# MAX_M10M_PINOUT.net
KiCad netlist of a schematic drawn in Altium Designer
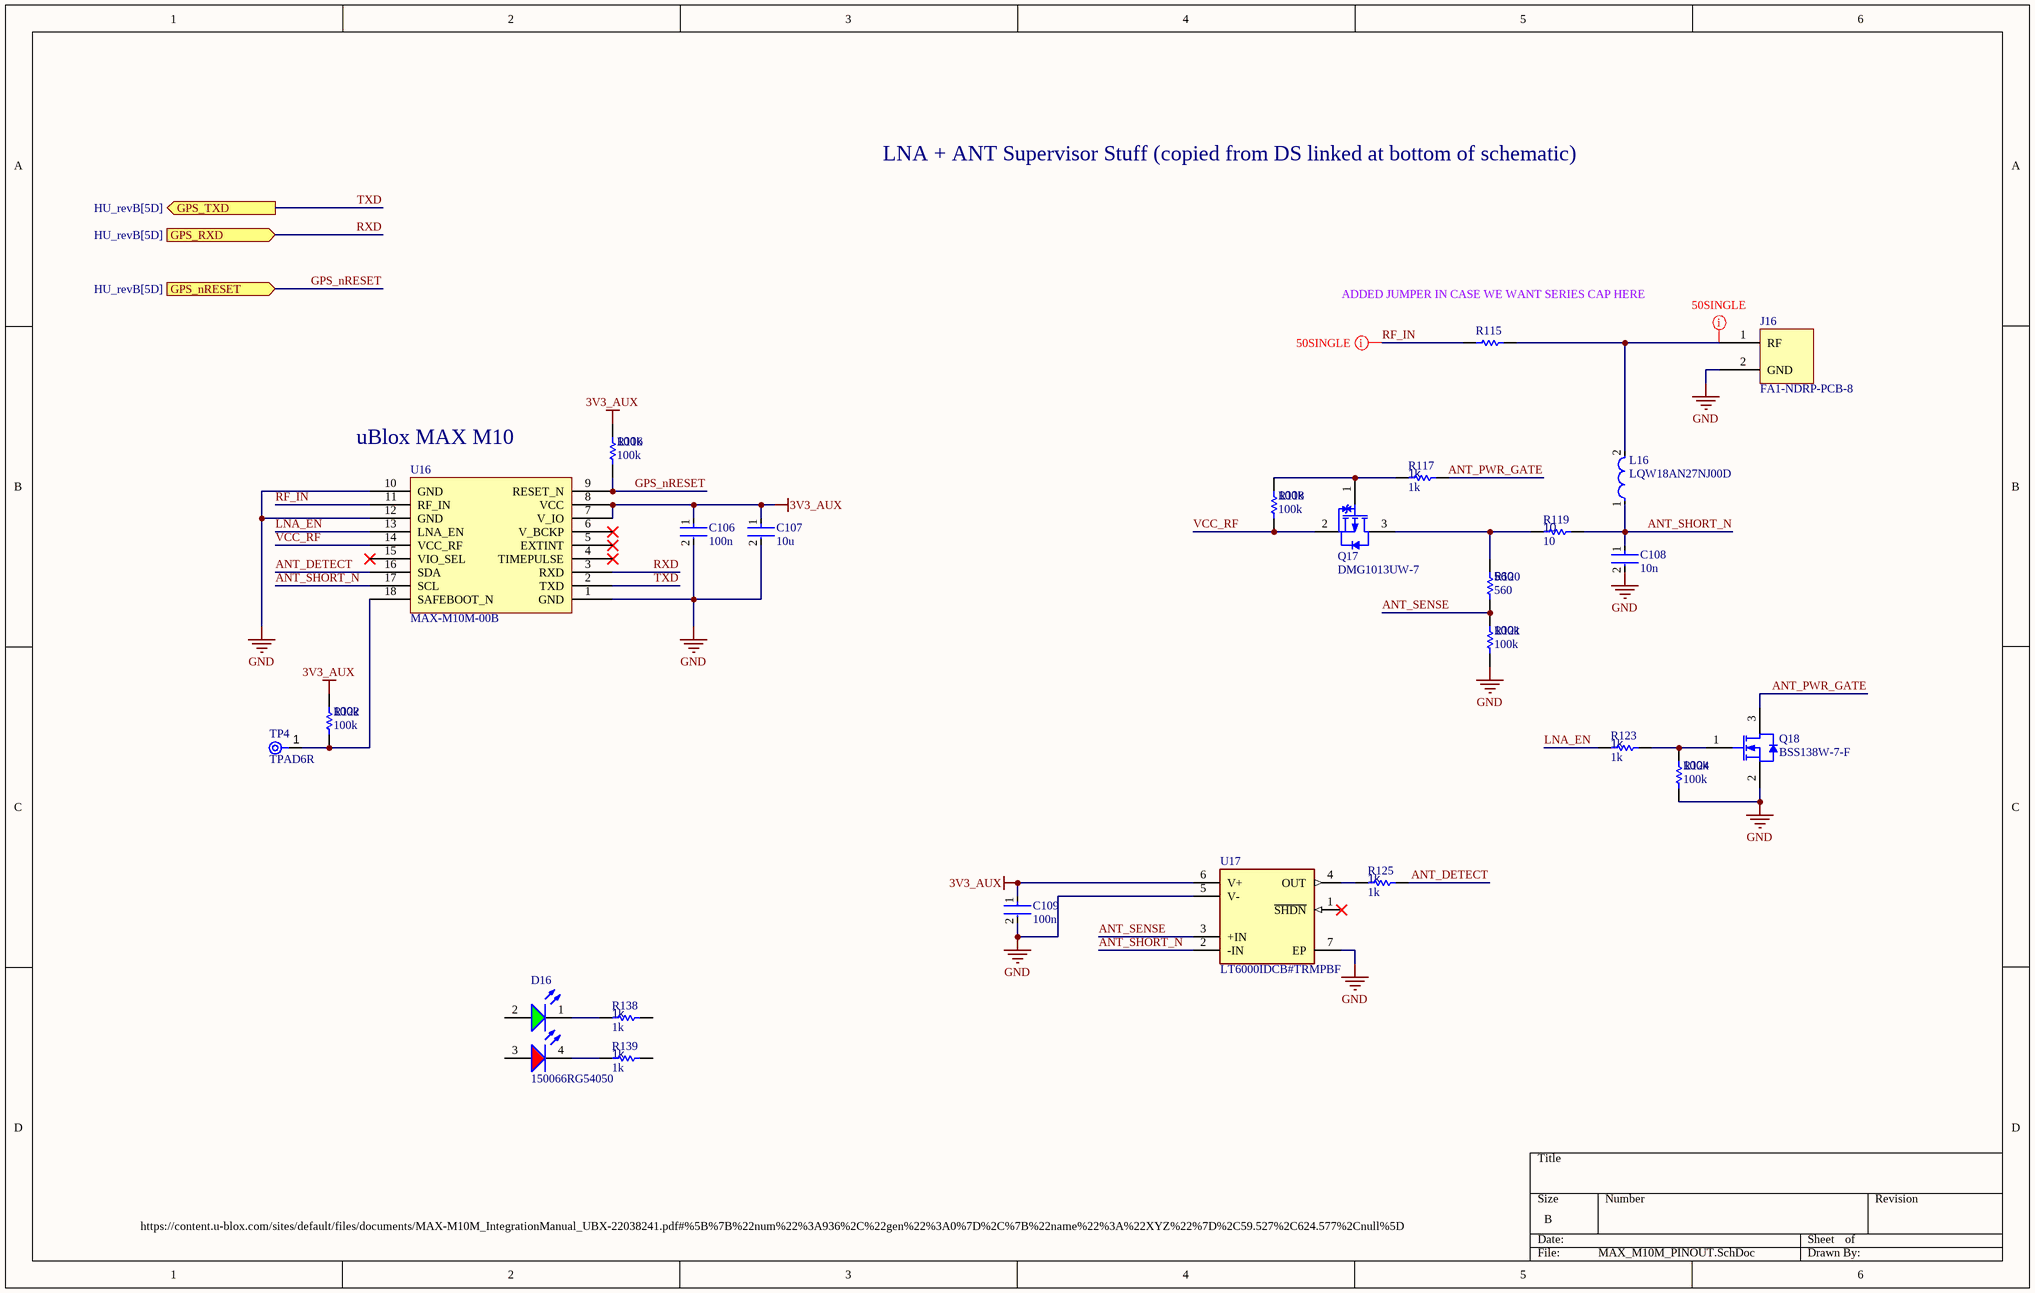
[diagram p0: MAX_M10M_PINOUT.SchDoc]

(export (version "E")
  (design (tool "Eeschema 10.0.6"))
  (components
    (comp (ref "C106")
      (value "100n")
      (footprint "FP-0402-L_1_0_0_05-W_0_5-IPC_A")
      (description "LARGE PADS, 0402 CAP, CHANGE COMMENT TO MATCH REAL P/N")
      (libsource (lib "Space Concordia") (part "b4654b650e69147ec39a6b967a45e02"))
    )
    (comp (ref "C107")
      (value "10u")
      (footprint "FP-0402-L_1_0_0_05-W_0_5-IPC_A")
      (description "LARGE PADS, 0402 CAP, CHANGE COMMENT TO MATCH REAL P/N")
      (libsource (lib "Space Concordia") (part "b4654b650e69147ec39a6b967a45e02"))
    )
    (comp (ref "C108")
      (value "10n")
      (footprint "FP-0402-L_1_0_0_05-W_0_5-IPC_A")
      (description "LARGE PADS, 0402 CAP, CHANGE COMMENT TO MATCH REAL P/N")
      (libsource (lib "Space Concordia") (part "b4654b650e69147ec39a6b967a45e02"))
    )
    (comp (ref "C109")
      (value "100n")
      (footprint "FP-0402-L_1_0_0_05-W_0_5-IPC_A")
      (description "LARGE PADS, 0402 CAP, CHANGE COMMENT TO MATCH REAL P/N")
      (libsource (lib "Space Concordia") (part "b4654b650e69147ec39a6b967a45e02"))
    )
    (comp (ref "D16")
      (value "150066RG54050")
      (footprint "WL-SBCD_0606")
      (description "Led, Red/Grn, 180Mcd/230Mcd, 624Nm/525Nm Rohs Compliant: Yes")
      (fields (field (name "SOURCE") "rgled.SchLib"))
      (libsource (lib "Space Concordia") (part "CMP-004-00034-2"))
    )
    (comp (ref "J16")
      (value "FA1-NDRP-PCB-8")
      (footprint "FA1-NDRP-PCB-8-Footprint-1")
      (description "RF F Connector, Male, Board Mount, Solder Terminal, Plug")
      (libsource (lib "Space Concordia") (part "FA1-NDRP-PCB-8"))
    )
    (comp (ref "L16")
      (value "LQW18AN27NJ00D")
      (footprint "FP-LQW18AN_00-MFG")
      (description "Wire Wound RF Inductor 27nH ±5% 440mA 0.21Ω 0603 (1608)")
      (fields (field (name "TOLERANCE") "5%"))
      (libsource (lib "Altium Content Vault") (part "725321dda6339637d4d059423bc1c3c"))
    )
    (comp (ref "Q17")
      (value "DMG1013UW-7")
      (footprint "DIOD-SOT323-3_V")
      (fields (field (name "MANUFACTURER") "Diodes Inc"))
      (libsource (lib "Altium Content Vault") (part "PEMOS-GSD-3_C"))
    )
    (comp (ref "Q18")
      (value "BSS138W-7-F")
      (footprint "DIOD-SOT323-3_V")
      (fields (field (name "MANUFACTURER") "DiodesIncorporated"))
      (libsource (lib "Altium Content Vault") (part "NEMOS-GSD-3"))
    )
    (comp (ref "R115")
      (value "0402 JUMPER")
      (footprint "RESC1005X40X25ML05T05")
      (description "READ THE NAME")
      (libsource (lib "Space Concordia") (part "CMP-009-00206-2"))
    )
    (comp (ref "R116")
      (value "100k")
      (footprint "R0603B")
      (description "Resistor")
      (fields (field (name "ALTIUM_VALUE") "100k"))
      (libsource (lib "Space Concordia") (part "Resistor"))
    )
    (comp (ref "R117")
      (value "1k")
      (footprint "R0603B")
      (description "Resistor")
      (fields (field (name "ALTIUM_VALUE") "1k"))
      (libsource (lib "Space Concordia") (part "Resistor"))
    )
    (comp (ref "R118")
      (value "100k")
      (footprint "R0603B")
      (description "Resistor")
      (fields (field (name "ALTIUM_VALUE") "100k"))
      (libsource (lib "Space Concordia") (part "Resistor"))
    )
    (comp (ref "R119")
      (value "10")
      (footprint "R0603B")
      (description "Resistor")
      (fields (field (name "ALTIUM_VALUE") "10"))
      (libsource (lib "Space Concordia") (part "Resistor"))
    )
    (comp (ref "R120")
      (value "560")
      (footprint "R0603B")
      (description "Resistor")
      (fields (field (name "ALTIUM_VALUE") "560"))
      (libsource (lib "Space Concordia") (part "Resistor"))
    )
    (comp (ref "R121")
      (value "100k")
      (footprint "R0603B")
      (description "Resistor")
      (fields (field (name "ALTIUM_VALUE") "100k"))
      (libsource (lib "Space Concordia") (part "Resistor"))
    )
    (comp (ref "R122")
      (value "100k")
      (footprint "R0603B")
      (description "Resistor")
      (fields (field (name "ALTIUM_VALUE") "100k"))
      (libsource (lib "Space Concordia") (part "Resistor"))
    )
    (comp (ref "R123")
      (value "1k")
      (footprint "R0603B")
      (description "Resistor")
      (fields (field (name "ALTIUM_VALUE") "1k"))
      (libsource (lib "Space Concordia") (part "Resistor"))
    )
    (comp (ref "R124")
      (value "100k")
      (footprint "R0603B")
      (description "Resistor")
      (fields (field (name "ALTIUM_VALUE") "100k"))
      (libsource (lib "Space Concordia") (part "Resistor"))
    )
    (comp (ref "R125")
      (value "1k")
      (footprint "R0603B")
      (description "Resistor")
      (fields (field (name "ALTIUM_VALUE") "1k"))
      (libsource (lib "Space Concordia") (part "Resistor"))
    )
    (comp (ref "R138")
      (value "1k")
      (footprint "R0603B")
      (description "Resistor")
      (fields (field (name "ALTIUM_VALUE") "1k"))
      (libsource (lib "Space Concordia") (part "Resistor"))
    )
    (comp (ref "R139")
      (value "1k")
      (footprint "R0603B")
      (description "Resistor")
      (fields (field (name "ALTIUM_VALUE") "1k"))
      (libsource (lib "Space Concordia") (part "Resistor"))
    )
    (comp (ref "TP4")
      (value "TPAD6R")
      (footprint "New footprint 1")
      (description "Test Point .6mm")
      (libsource (lib "Space Concordia") (part "TP"))
    )
    (comp (ref "U16")
      (value "MAX-M10M-00B")
      (footprint "MAX-M10M-00B-Footprint-1")
      (description "Gnss Lcc Rx Mod, Rom, Crystal")
      (libsource (lib "Space Concordia") (part "MAX-M10M-00B"))
    )
    (comp (ref "U17")
      (value "LT6000IDCB#TRMPBF")
      (footprint "FP-DCB-6-05-08-1715-MFG")
      (description "IC OPAMP GP 1 CIRCUIT 6DFN")
      (libsource (lib "Altium Content Vault") (part "33bb285994f2e703f79bf9d86341a8a"))
    )
  )
  (nets
    (net (code "1") (name "/ANT_DETECT") (class "Default")
      (node (ref "R125") (pin "2") (pinfunction "2_2") (pintype "passive"))
      (node (ref "U16") (pin "16") (pinfunction "SDA_16") (pintype "passive"))
    )
    (net (code "2") (name "/ANT_PWR_GATE") (class "Default")
      (node (ref "Q18") (pin "3") (pinfunction "D_3") (pintype "passive"))
      (node (ref "R117") (pin "2") (pinfunction "2_2") (pintype "passive"))
    )
    (net (code "3") (name "/ANT_SENSE") (class "Default")
      (node (ref "R120") (pin "2") (pinfunction "2_2") (pintype "passive"))
      (node (ref "R121") (pin "1") (pinfunction "1_1") (pintype "passive"))
      (node (ref "U17") (pin "3") (pinfunction "+IN_3") (pintype "tri_state"))
    )
    (net (code "4") (name "/ANT_SHORT_N") (class "Default")
      (node (ref "C108") (pin "1") (pinfunction "1_1") (pintype "passive"))
      (node (ref "L16") (pin "1") (pinfunction "1_1") (pintype "passive"))
      (node (ref "R119") (pin "2") (pinfunction "2_2") (pintype "passive"))
      (node (ref "U16") (pin "17") (pinfunction "SCL_17") (pintype "passive"))
      (node (ref "U17") (pin "2") (pinfunction "-IN_2") (pintype "tri_state"))
    )
    (net (code "5") (name "/GPS_nRESET") (class "Default")
      (node (ref "R116") (pin "2") (pinfunction "2_2") (pintype "passive"))
      (node (ref "U16") (pin "9") (pinfunction "RESET_N_9") (pintype "passive"))
    )
    (net (code "6") (name "/LNA_EN") (class "Default")
      (node (ref "R123") (pin "1") (pinfunction "1_1") (pintype "passive"))
      (node (ref "U16") (pin "13") (pinfunction "LNA_EN_13") (pintype "passive"))
    )
    (net (code "7") (name "/RF_IN") (class "Default")
      (node (ref "R115") (pin "1") (pinfunction "1_1") (pintype "passive"))
      (node (ref "U16") (pin "11") (pinfunction "RF_IN_11") (pintype "passive"))
    )
    (net (code "8") (name "/RXD") (class "Default")
      (node (ref "U16") (pin "3") (pinfunction "RXD_3") (pintype "passive"))
    )
    (net (code "9") (name "/TXD") (class "Default")
      (node (ref "U16") (pin "2") (pinfunction "TXD_2") (pintype "passive"))
    )
    (net (code "10") (name "/VCC_RF") (class "Default")
      (node (ref "Q17") (pin "2") (pinfunction "S_2") (pintype "passive"))
      (node (ref "R118") (pin "2") (pinfunction "2_2") (pintype "passive"))
      (node (ref "U16") (pin "14") (pinfunction "VCC_RF_14") (pintype "passive"))
    )
    (net (code "11") (name "3V3_AUX") (class "Default")
      (node (ref "C106") (pin "1") (pinfunction "1_1") (pintype "passive"))
      (node (ref "C107") (pin "1") (pinfunction "1_1") (pintype "passive"))
      (node (ref "C109") (pin "1") (pinfunction "1_1") (pintype "passive"))
      (node (ref "R116") (pin "1") (pinfunction "1_1") (pintype "passive"))
      (node (ref "R122") (pin "1") (pinfunction "1_1") (pintype "passive"))
      (node (ref "U16") (pin "7") (pinfunction "V_IO_7") (pintype "passive"))
      (node (ref "U16") (pin "8") (pinfunction "VCC_8") (pintype "passive"))
      (node (ref "U17") (pin "6") (pinfunction "V+_6") (pintype "power_in"))
    )
    (net (code "12") (name "GND") (class "Default")
      (node (ref "C106") (pin "2") (pinfunction "2_2") (pintype "passive"))
      (node (ref "C107") (pin "2") (pinfunction "2_2") (pintype "passive"))
      (node (ref "C108") (pin "2") (pinfunction "2_2") (pintype "passive"))
      (node (ref "C109") (pin "2") (pinfunction "2_2") (pintype "passive"))
      (node (ref "J16") (pin "2") (pinfunction "GND_2") (pintype "passive"))
      (node (ref "Q18") (pin "2") (pinfunction "S_2") (pintype "passive"))
      (node (ref "R121") (pin "2") (pinfunction "2_2") (pintype "passive"))
      (node (ref "R124") (pin "2") (pinfunction "2_2") (pintype "passive"))
      (node (ref "U16") (pin "1") (pinfunction "GND_1") (pintype "passive"))
      (node (ref "U16") (pin "10") (pinfunction "GND_10") (pintype "passive"))
      (node (ref "U16") (pin "12") (pinfunction "GND_12") (pintype "passive"))
      (node (ref "U17") (pin "5") (pinfunction "V-_5") (pintype "power_in"))
      (node (ref "U17") (pin "7") (pinfunction "EP_7") (pintype "power_in"))
    )
    (net (code "13") (name "Net-(D16-K-Pad1)") (class "Default")
      (node (ref "D16") (pin "1") (pinfunction "K_1") (pintype "passive"))
      (node (ref "R138") (pin "2") (pinfunction "2_2") (pintype "passive"))
    )
    (net (code "14") (name "Net-(D16-K-Pad4)") (class "Default")
      (node (ref "D16") (pin "4") (pinfunction "K_4") (pintype "passive"))
      (node (ref "R139") (pin "2") (pinfunction "2_2") (pintype "passive"))
    )
    (net (code "15") (name "Net-(J16-RF)") (class "Default")
      (node (ref "J16") (pin "1") (pinfunction "RF_1") (pintype "passive"))
      (node (ref "L16") (pin "2") (pinfunction "2_2") (pintype "passive"))
      (node (ref "R115") (pin "2") (pinfunction "2_2") (pintype "passive"))
    )
    (net (code "16") (name "Net-(Q17-D)") (class "Default")
      (node (ref "Q17") (pin "3") (pinfunction "D_3") (pintype "passive"))
      (node (ref "R119") (pin "1") (pinfunction "1_1") (pintype "passive"))
      (node (ref "R120") (pin "1") (pinfunction "1_1") (pintype "passive"))
    )
    (net (code "17") (name "Net-(Q17-G)") (class "Default")
      (node (ref "Q17") (pin "1") (pinfunction "G_1") (pintype "passive"))
      (node (ref "R117") (pin "1") (pinfunction "1_1") (pintype "passive"))
      (node (ref "R118") (pin "1") (pinfunction "1_1") (pintype "passive"))
    )
    (net (code "18") (name "Net-(Q18-G)") (class "Default")
      (node (ref "Q18") (pin "1") (pinfunction "G_1") (pintype "passive"))
      (node (ref "R123") (pin "2") (pinfunction "2_2") (pintype "passive"))
      (node (ref "R124") (pin "1") (pinfunction "1_1") (pintype "passive"))
    )
    (net (code "19") (name "Net-(TP4-TP)") (class "Default")
      (node (ref "R122") (pin "2") (pinfunction "2_2") (pintype "passive"))
      (node (ref "TP4") (pin "1") (pinfunction "TP_1") (pintype "passive"))
      (node (ref "U16") (pin "18") (pinfunction "SAFEBOOT_N_18") (pintype "passive"))
    )
    (net (code "20") (name "Net-(U17-OUT)") (class "Default")
      (node (ref "R125") (pin "1") (pinfunction "1_1") (pintype "passive"))
      (node (ref "U17") (pin "4") (pinfunction "OUT_4") (pintype "output"))
    )
    (net (code "21") (name "unconnected-(D16-A-Pad2)") (class "Default")
      (node (ref "D16") (pin "2") (pinfunction "A_2") (pintype "passive"))
    )
    (net (code "22") (name "unconnected-(D16-A-Pad3)") (class "Default")
      (node (ref "D16") (pin "3") (pinfunction "A_3") (pintype "passive"))
    )
    (net (code "23") (name "unconnected-(R138-Pad1)") (class "Default")
      (node (ref "R138") (pin "1") (pinfunction "1_1") (pintype "passive"))
    )
    (net (code "24") (name "unconnected-(R139-Pad1)") (class "Default")
      (node (ref "R139") (pin "1") (pinfunction "1_1") (pintype "passive"))
    )
    (net (code "25") (name "unconnected-(U16-EXTINT-Pad5)") (class "Default")
      (node (ref "U16") (pin "5") (pinfunction "EXTINT_5") (pintype "passive+no_connect"))
    )
    (net (code "26") (name "unconnected-(U16-TIMEPULSE-Pad4)") (class "Default")
      (node (ref "U16") (pin "4") (pinfunction "TIMEPULSE_4") (pintype "passive+no_connect"))
    )
    (net (code "27") (name "unconnected-(U16-VIO_SEL-Pad15)") (class "Default")
      (node (ref "U16") (pin "15") (pinfunction "VIO_SEL_15") (pintype "passive+no_connect"))
    )
    (net (code "28") (name "unconnected-(U16-V_BCKP-Pad6)") (class "Default")
      (node (ref "U16") (pin "6") (pinfunction "V_BCKP_6") (pintype "passive+no_connect"))
    )
    (net (code "29") (name "unconnected-(U17-~{SHDN}-Pad1)") (class "Default")
      (node (ref "U17") (pin "1") (pinfunction "~{SHDN}_1") (pintype "input+no_connect"))
    )
  )
)
